# jeu_du_moulin_boura_uP_SCH.net
KiCad netlist of a schematic drawn in Altium Designer
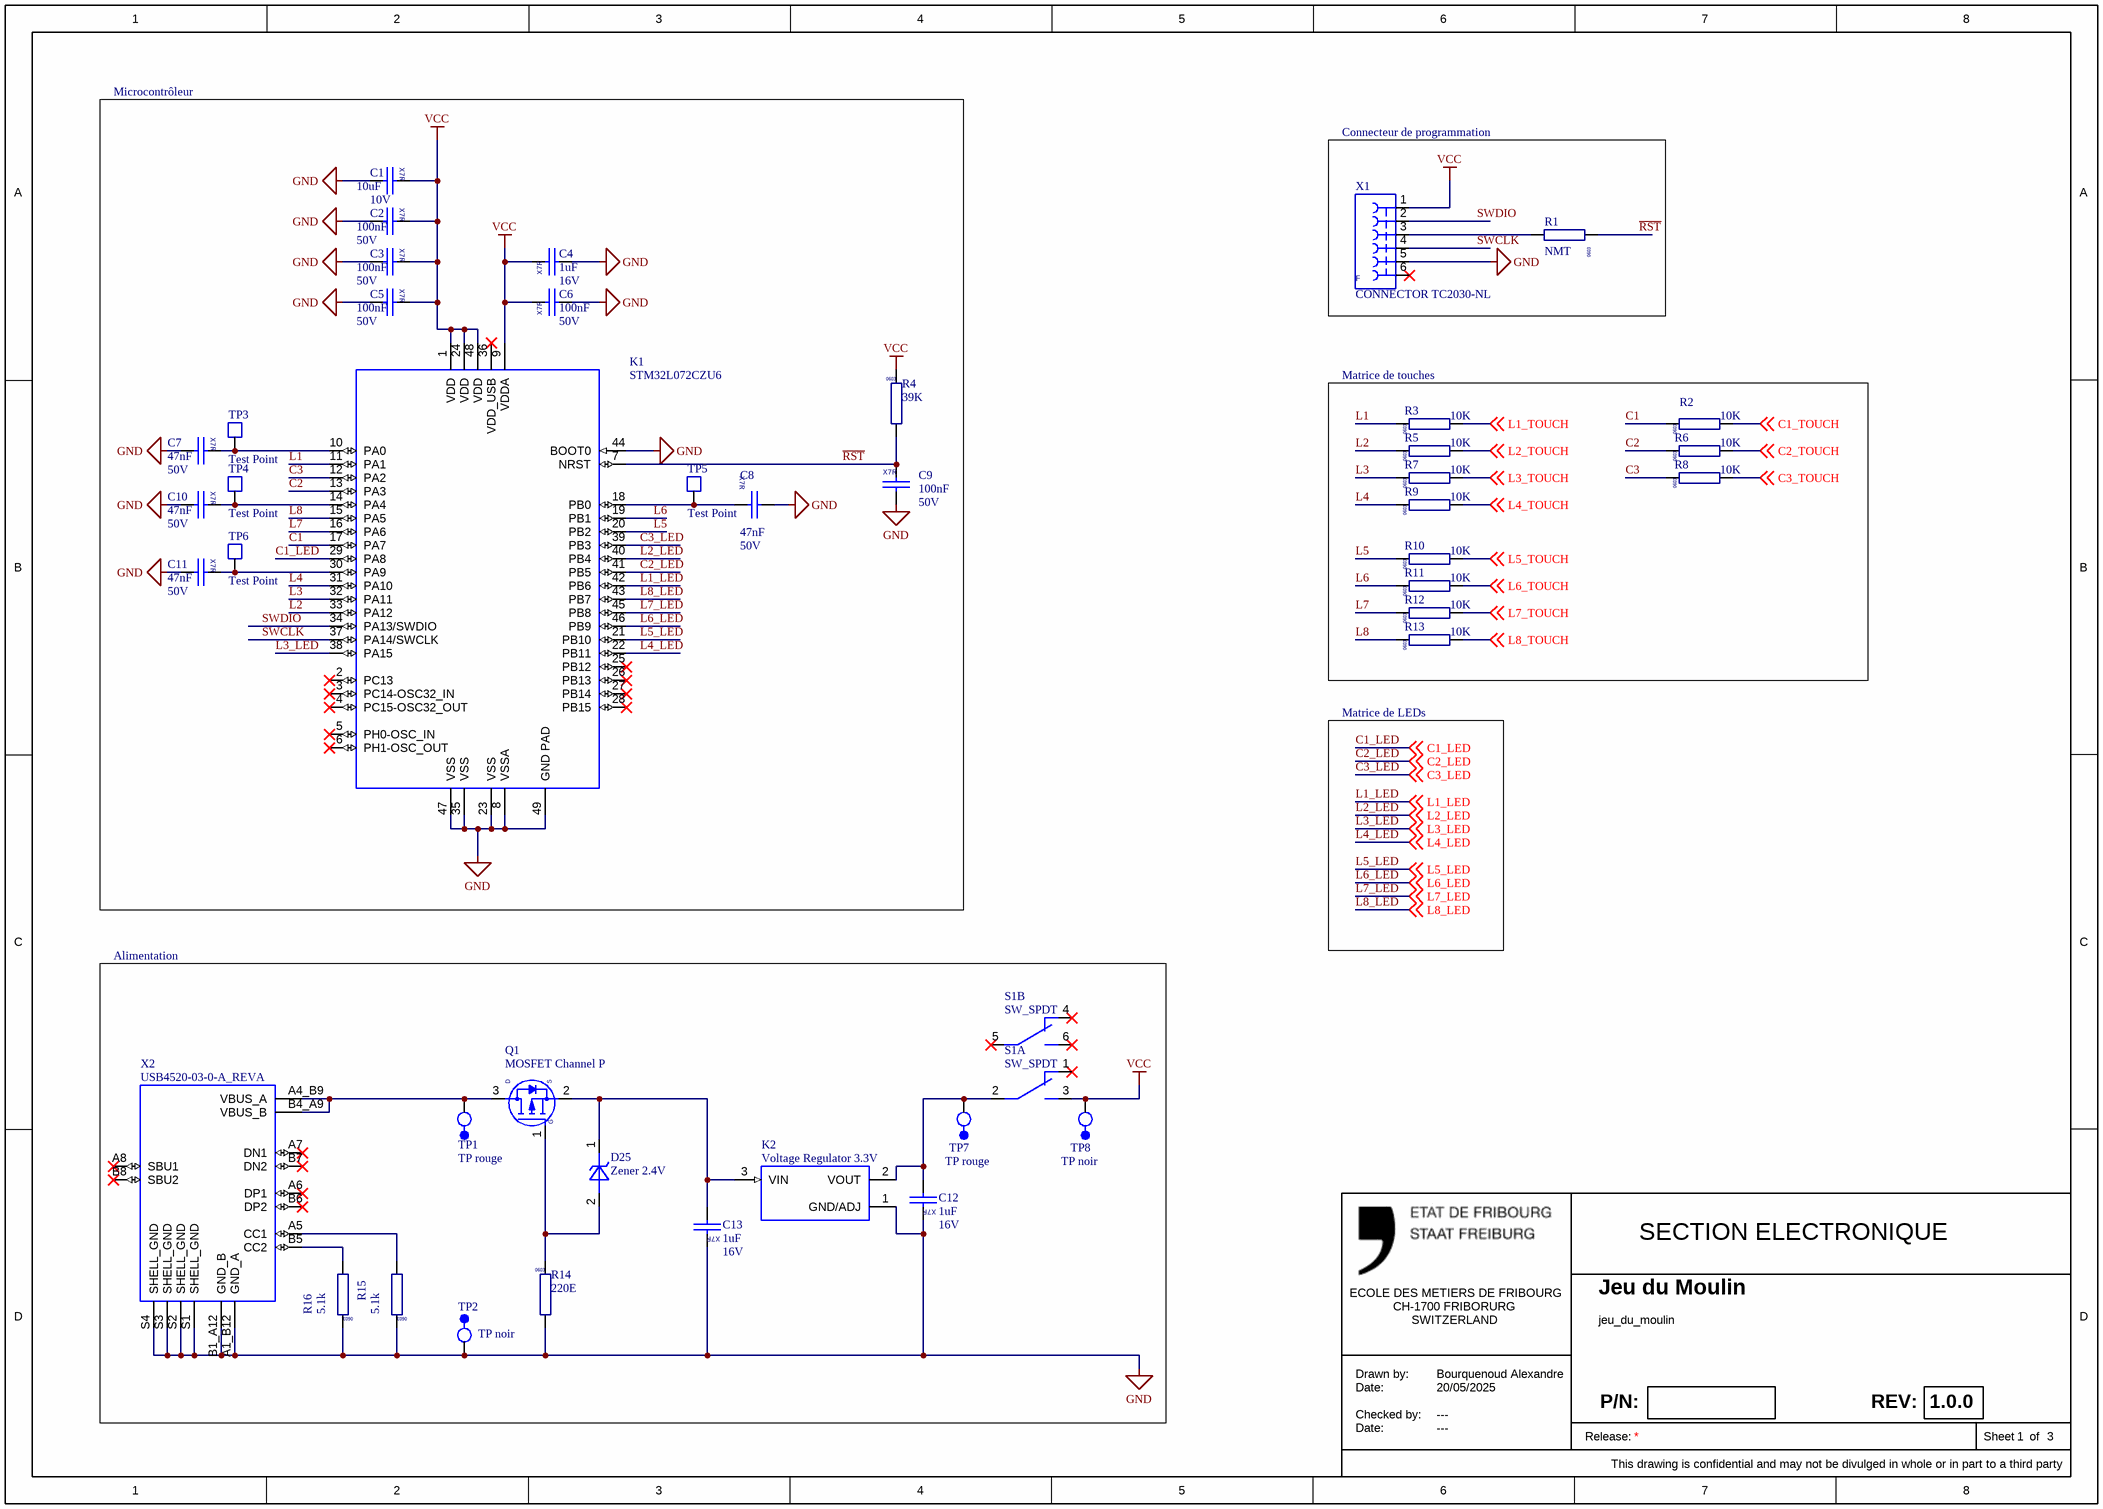
[diagram p0: jeu_du_moulin_boura_uP_SCH.SchDoc]

(export (version "E")
  (design (tool "Eeschema 10.0.6"))
  (components
    (comp (ref "C1")
      (value "10uF")
      (footprint "CSMD0603")
      (description "C X5R 10uF 20% 10V 0603")
      (fields (field (name "VOLT") "10V"))
      (libsource (lib "EMF_DataBase") (part "E_COND-X7R"))
    )
    (comp (ref "C2")
      (value "100nF")
      (footprint "CSMD0603")
      (description "C X7R 0.1uF 10% 50V 0603")
      (fields (field (name "VOLT") "50V"))
      (libsource (lib "EMF_DataBase") (part "E_COND-X7R"))
    )
    (comp (ref "C3")
      (value "100nF")
      (footprint "CSMD0603")
      (description "C X7R 0.1uF 10% 50V 0603")
      (fields (field (name "VOLT") "50V"))
      (libsource (lib "EMF_DataBase") (part "E_COND-X7R"))
    )
    (comp (ref "C4")
      (value "1uF")
      (footprint "CSMD0603")
      (description "C X7R 1uF 10% 16V 0603")
      (fields (field (name "VOLT") "16V"))
      (libsource (lib "EMF_DataBase") (part "E_COND-X7R"))
    )
    (comp (ref "C5")
      (value "100nF")
      (footprint "CSMD0603")
      (description "C X7R 0.1uF 10% 50V 0603")
      (fields (field (name "VOLT") "50V"))
      (libsource (lib "EMF_DataBase") (part "E_COND-X7R"))
    )
    (comp (ref "C6")
      (value "100nF")
      (footprint "CSMD0603")
      (description "C X7R 0.1uF 10% 50V 0603")
      (fields (field (name "VOLT") "50V"))
      (libsource (lib "EMF_DataBase") (part "E_COND-X7R"))
    )
    (comp (ref "C7")
      (value "47nF")
      (footprint "CSMD0603")
      (description "C X7R 47nF 10% 50V 0603")
      (fields (field (name "VOLT") "50V"))
      (libsource (lib "EMF_DataBase") (part "E_COND-X7R"))
    )
    (comp (ref "C8")
      (value "47nF")
      (footprint "CSMD0603")
      (description "C X7R 47nF 10% 50V 0603")
      (fields (field (name "VOLT") "50V"))
      (libsource (lib "EMF_DataBase") (part "E_COND-X7R"))
    )
    (comp (ref "C9")
      (value "100nF")
      (footprint "CSMD0603")
      (description "C X7R 0.1uF 10% 50V 0603")
      (fields (field (name "VOLT") "50V"))
      (libsource (lib "EMF_DataBase") (part "E_COND-X7R"))
    )
    (comp (ref "C10")
      (value "47nF")
      (footprint "CSMD0603")
      (description "C X7R 47nF 10% 50V 0603")
      (fields (field (name "VOLT") "50V"))
      (libsource (lib "EMF_DataBase") (part "E_COND-X7R"))
    )
    (comp (ref "C11")
      (value "47nF")
      (footprint "CSMD0603")
      (description "C X7R 47nF 10% 50V 0603")
      (fields (field (name "VOLT") "50V"))
      (libsource (lib "EMF_DataBase") (part "E_COND-X7R"))
    )
    (comp (ref "C12")
      (value "1uF")
      (footprint "CSMD0603")
      (description "C X7R 1uF 10% 16V 0603")
      (fields (field (name "VOLT") "16V"))
      (libsource (lib "EMF_DataBase") (part "E_COND-X7R"))
    )
    (comp (ref "C13")
      (value "1uF")
      (footprint "CSMD0603")
      (description "C X7R 1uF 10% 16V 0603")
      (fields (field (name "VOLT") "16V"))
      (libsource (lib "EMF_DataBase") (part "E_COND-X7R"))
    )
    (comp (ref "D25")
      (value "Zener 2.4V")
      (footprint "SOD-123")
      (description "Diodes - Zener 2.4 V 500 mW ±5% Montage en surface SOD-123")
      (libsource (lib "jeu_du_moulin_boura_INTLIB") (part "Zener 2.4V"))
    )
    (comp (ref "K1")
      (value "STM32L072CZU6")
      (footprint "UFQFPN48")
      (description "IC MCU 32BIT 192KB FLASH UFQFPN48s")
      (libsource (lib "jeu_du_moulin_boura_INTLIB") (part "STM32L072CZU6"))
    )
    (comp (ref "K2")
      (value "Voltage Regulator 3.3V")
      (footprint "SOT95P240X88-3N")
      (description "3.3-Volt Low Drop Out Voltage Regulatator")
      (libsource (lib "jeu_du_moulin_boura_INTLIB") (part "Voltage Regulator 3.3V"))
    )
    (comp (ref "Q1")
      (value "MOSFET Channel P")
      (footprint "SOT95P240X88-3N")
      (description "MOSFET Pch -80V -10A TO-252, Power MOSFET")
      (libsource (lib "jeu_du_moulin_boura_INTLIB") (part "MOSFET Channel P"))
    )
    (comp (ref "R1")
      (value "NMT")
      (footprint "RSMD0603")
      (description "R SMD NOT MOUNTED  1% 60mW  CHIP 0603")
      (fields (field (name "POWER") "60mW"))
      (libsource (lib "") (part "E_RSMD0603_1"))
    )
    (comp (ref "R2")
      (value "10K")
      (footprint "RSMD0603")
      (description "R SMD 10K  1%  60mW  CHIP 0603")
      (fields (field (name "POWER") "60mW"))
      (libsource (lib "EMF_DataBase") (part "E_RSMD0603"))
    )
    (comp (ref "R3")
      (value "10K")
      (footprint "RSMD0603")
      (description "R SMD 10K  1%  60mW  CHIP 0603")
      (fields (field (name "POWER") "60mW"))
      (libsource (lib "EMF_DataBase") (part "E_RSMD0603"))
    )
    (comp (ref "R4")
      (value "39K")
      (footprint "RSMD0603")
      (description "R SMD 39K  1%  60mW  CHIP 0603")
      (fields (field (name "POWER") "60mW"))
      (libsource (lib "") (part "E_RSMD0603_1"))
    )
    (comp (ref "R5")
      (value "10K")
      (footprint "RSMD0603")
      (description "R SMD 10K  1%  60mW  CHIP 0603")
      (fields (field (name "POWER") "60mW"))
      (libsource (lib "EMF_DataBase") (part "E_RSMD0603"))
    )
    (comp (ref "R6")
      (value "10K")
      (footprint "RSMD0603")
      (description "R SMD 10K  1%  60mW  CHIP 0603")
      (fields (field (name "POWER") "60mW"))
      (libsource (lib "EMF_DataBase") (part "E_RSMD0603"))
    )
    (comp (ref "R7")
      (value "10K")
      (footprint "RSMD0603")
      (description "R SMD 10K  1%  60mW  CHIP 0603")
      (fields (field (name "POWER") "60mW"))
      (libsource (lib "EMF_DataBase") (part "E_RSMD0603"))
    )
    (comp (ref "R8")
      (value "10K")
      (footprint "RSMD0603")
      (description "R SMD 10K  1%  60mW  CHIP 0603")
      (fields (field (name "POWER") "60mW"))
      (libsource (lib "EMF_DataBase") (part "E_RSMD0603"))
    )
    (comp (ref "R9")
      (value "10K")
      (footprint "RSMD0603")
      (description "R SMD 10K  1%  60mW  CHIP 0603")
      (fields (field (name "POWER") "60mW"))
      (libsource (lib "EMF_DataBase") (part "E_RSMD0603"))
    )
    (comp (ref "R10")
      (value "10K")
      (footprint "RSMD0603")
      (description "R SMD 10K  1%  60mW  CHIP 0603")
      (fields (field (name "POWER") "60mW"))
      (libsource (lib "EMF_DataBase") (part "E_RSMD0603"))
    )
    (comp (ref "R11")
      (value "10K")
      (footprint "RSMD0603")
      (description "R SMD 10K  1%  60mW  CHIP 0603")
      (fields (field (name "POWER") "60mW"))
      (libsource (lib "EMF_DataBase") (part "E_RSMD0603"))
    )
    (comp (ref "R12")
      (value "10K")
      (footprint "RSMD0603")
      (description "R SMD 10K  1%  60mW  CHIP 0603")
      (fields (field (name "POWER") "60mW"))
      (libsource (lib "EMF_DataBase") (part "E_RSMD0603"))
    )
    (comp (ref "R13")
      (value "10K")
      (footprint "RSMD0603")
      (description "R SMD 10K  1%  60mW  CHIP 0603")
      (fields (field (name "POWER") "60mW"))
      (libsource (lib "EMF_DataBase") (part "E_RSMD0603"))
    )
    (comp (ref "R14")
      (value "220E")
      (footprint "RSMD0603")
      (description "R SMD 220E  1% 60mW  CHIP 0603")
      (fields (field (name "POWER") "60mW"))
      (libsource (lib "") (part "E_RSMD0603_1"))
    )
    (comp (ref "R15")
      (value "5.1k")
      (footprint "RSMD0603")
      (description "5.1 kOhms ±1% 0,1W, 1/10W Pavé résistif 0603 (1608 métrique) AutomobileAEC-Q200 Couche épaisse")
      (libsource (lib "jeu_du_moulin_boura_INTLIB") (part "5.1k"))
    )
    (comp (ref "R16")
      (value "5.1k")
      (footprint "RSMD0603")
      (description "5.1 kOhms ±1% 0,1W, 1/10W Pavé résistif 0603 (1608 métrique) AutomobileAEC-Q200 Couche épaisse")
      (libsource (lib "jeu_du_moulin_boura_INTLIB") (part "5.1k"))
    )
    (comp (ref "S1")
      (value "SW_SPDT")
      (footprint "Switch Slide DPDT")
      (description "Switch slide SPDT 300mA 6V")
      (libsource (lib "jeu_du_moulin_boura_INTLIB") (part "SW_SPDT"))
    )
    (comp (ref "TP1")
      (value "TP rouge")
      (footprint "TP10_22")
      (description "Point de test CI isolé rouge")
      (libsource (lib "EMF_DataBase") (part "E_TestPoint_Sonde"))
    )
    (comp (ref "TP2")
      (value "TP noir")
      (footprint "TP10_22")
      (description "Point de test CI isolé noir")
      (libsource (lib "EMF_DataBase") (part "E_TestPoint_Sonde"))
    )
    (comp (ref "TP3")
      (value "Test Point")
      (footprint "TP")
      (description "Point de Test SMD")
      (libsource (lib "jeu_du_moulin_boura_INTLIB") (part "Test Point"))
    )
    (comp (ref "TP4")
      (value "Test Point")
      (footprint "TP")
      (description "Point de Test SMD")
      (libsource (lib "jeu_du_moulin_boura_INTLIB") (part "Test Point"))
    )
    (comp (ref "TP5")
      (value "Test Point")
      (footprint "TP")
      (description "Point de Test SMD")
      (libsource (lib "jeu_du_moulin_boura_INTLIB") (part "Test Point"))
    )
    (comp (ref "TP6")
      (value "Test Point")
      (footprint "TP")
      (description "Point de Test SMD")
      (libsource (lib "jeu_du_moulin_boura_INTLIB") (part "Test Point"))
    )
    (comp (ref "TP7")
      (value "TP rouge")
      (footprint "TP10_22")
      (description "Point de test CI isolé rouge")
      (libsource (lib "EMF_DataBase") (part "E_TestPoint_Sonde"))
    )
    (comp (ref "TP8")
      (value "TP noir")
      (footprint "TP10_22")
      (description "Point de test CI isolé noir")
      (libsource (lib "EMF_DataBase") (part "E_TestPoint_Sonde"))
    )
    (comp (ref "X1")
      (value "CONNECTOR TC2030-NL")
      (footprint "T-Connect 2030")
      (description "Connecteur pour TC2030-NL")
      (libsource (lib "jeu_du_moulin_boura_INTLIB") (part "CONNECTOR TC2030-NL"))
    )
    (comp (ref "X2")
      (value "USB4520-03-0-A_REVA")
      (footprint "GCT_USB4520-03-0-A_REVA")
      (libsource (lib "jeu_du_moulin_boura_INTLIB") (part "USB4520-03-0-A_REVA"))
    )
  )
  (nets
    (net (code "1") (name "/C1") (class "Default")
      (node (ref "K1") (pin "17") (pinfunction "PA7_17") (pintype "bidirectional"))
      (node (ref "R2") (pin "1") (pinfunction "1_1") (pintype "passive"))
    )
    (net (code "2") (name "/C2") (class "Default")
      (node (ref "K1") (pin "13") (pinfunction "PA3_13") (pintype "bidirectional"))
      (node (ref "R6") (pin "1") (pinfunction "1_1") (pintype "passive"))
    )
    (net (code "3") (name "/C3") (class "Default")
      (node (ref "K1") (pin "12") (pinfunction "PA2_12") (pintype "bidirectional"))
      (node (ref "R8") (pin "1") (pinfunction "1_1") (pintype "passive"))
    )
    (net (code "4") (name "/L1") (class "Default")
      (node (ref "K1") (pin "11") (pinfunction "PA1_11") (pintype "bidirectional"))
      (node (ref "R3") (pin "1") (pinfunction "1_1") (pintype "passive"))
    )
    (net (code "5") (name "/L2") (class "Default")
      (node (ref "K1") (pin "33") (pinfunction "PA12_33") (pintype "bidirectional"))
      (node (ref "R5") (pin "1") (pinfunction "1_1") (pintype "passive"))
    )
    (net (code "6") (name "/L3") (class "Default")
      (node (ref "K1") (pin "32") (pinfunction "PA11_32") (pintype "bidirectional"))
      (node (ref "R7") (pin "1") (pinfunction "1_1") (pintype "passive"))
    )
    (net (code "7") (name "/L4") (class "Default")
      (node (ref "K1") (pin "31") (pinfunction "PA10_31") (pintype "bidirectional"))
      (node (ref "R9") (pin "1") (pinfunction "1_1") (pintype "passive"))
    )
    (net (code "8") (name "/L5") (class "Default")
      (node (ref "K1") (pin "20") (pinfunction "PB2_20") (pintype "bidirectional"))
      (node (ref "R10") (pin "1") (pinfunction "1_1") (pintype "passive"))
    )
    (net (code "9") (name "/L6") (class "Default")
      (node (ref "K1") (pin "19") (pinfunction "PB1_19") (pintype "bidirectional"))
      (node (ref "R11") (pin "1") (pinfunction "1_1") (pintype "passive"))
    )
    (net (code "10") (name "/L7") (class "Default")
      (node (ref "K1") (pin "16") (pinfunction "PA6_16") (pintype "bidirectional"))
      (node (ref "R12") (pin "1") (pinfunction "1_1") (pintype "passive"))
    )
    (net (code "11") (name "/L8") (class "Default")
      (node (ref "K1") (pin "15") (pinfunction "PA5_15") (pintype "bidirectional"))
      (node (ref "R13") (pin "1") (pinfunction "1_1") (pintype "passive"))
    )
    (net (code "12") (name "/SWCLK") (class "Default")
      (node (ref "K1") (pin "37") (pinfunction "PA14/SWCLK_37") (pintype "bidirectional"))
      (node (ref "X1") (pin "4") (pinfunction "SWCLK_4") (pintype "passive"))
    )
    (net (code "13") (name "/SWDIO") (class "Default")
      (node (ref "K1") (pin "34") (pinfunction "PA13/SWDIO_34") (pintype "bidirectional"))
      (node (ref "X1") (pin "2") (pinfunction "SWDIO_2") (pintype "passive"))
    )
    (net (code "14") (name "/~{RST}") (class "Default")
      (node (ref "C9") (pin "1") (pinfunction "1_1") (pintype "passive"))
      (node (ref "K1") (pin "7") (pinfunction "NRST_7") (pintype "bidirectional"))
      (node (ref "R1") (pin "1") (pinfunction "1_1") (pintype "passive"))
      (node (ref "R4") (pin "2") (pinfunction "2_2") (pintype "passive"))
    )
    (net (code "15") (name "C1_LED") (class "Default")
      (node (ref "K1") (pin "29") (pinfunction "PA8_29") (pintype "bidirectional"))
    )
    (net (code "16") (name "C1_TOUCH") (class "Default")
      (node (ref "R2") (pin "2") (pinfunction "2_2") (pintype "passive"))
    )
    (net (code "17") (name "C2_LED") (class "Default")
      (node (ref "K1") (pin "41") (pinfunction "PB5_41") (pintype "bidirectional"))
    )
    (net (code "18") (name "C2_TOUCH") (class "Default")
      (node (ref "R6") (pin "2") (pinfunction "2_2") (pintype "passive"))
    )
    (net (code "19") (name "C3_LED") (class "Default")
      (node (ref "K1") (pin "39") (pinfunction "PB3_39") (pintype "bidirectional"))
    )
    (net (code "20") (name "C3_TOUCH") (class "Default")
      (node (ref "R8") (pin "2") (pinfunction "2_2") (pintype "passive"))
    )
    (net (code "21") (name "GND") (class "Default")
      (node (ref "C1") (pin "2") (pinfunction "2_2") (pintype "passive"))
      (node (ref "C10") (pin "2") (pinfunction "2_2") (pintype "passive"))
      (node (ref "C11") (pin "2") (pinfunction "2_2") (pintype "passive"))
      (node (ref "C12") (pin "1") (pinfunction "1_1") (pintype "passive"))
      (node (ref "C13") (pin "1") (pinfunction "1_1") (pintype "passive"))
      (node (ref "C2") (pin "2") (pinfunction "2_2") (pintype "passive"))
      (node (ref "C3") (pin "2") (pinfunction "2_2") (pintype "passive"))
      (node (ref "C4") (pin "2") (pinfunction "2_2") (pintype "passive"))
      (node (ref "C5") (pin "2") (pinfunction "2_2") (pintype "passive"))
      (node (ref "C6") (pin "2") (pinfunction "2_2") (pintype "passive"))
      (node (ref "C7") (pin "2") (pinfunction "2_2") (pintype "passive"))
      (node (ref "C8") (pin "2") (pinfunction "2_2") (pintype "passive"))
      (node (ref "C9") (pin "2") (pinfunction "2_2") (pintype "passive"))
      (node (ref "K1") (pin "23") (pinfunction "VSS_23") (pintype "power_in"))
      (node (ref "K1") (pin "35") (pinfunction "VSS_35") (pintype "power_in"))
      (node (ref "K1") (pin "44") (pinfunction "BOOT0_44") (pintype "input"))
      (node (ref "K1") (pin "47") (pinfunction "VSS_47") (pintype "power_in"))
      (node (ref "K1") (pin "49") (pinfunction "GND_PAD_49") (pintype "power_in"))
      (node (ref "K1") (pin "8") (pinfunction "VSSA_8") (pintype "power_in"))
      (node (ref "K2") (pin "1") (pinfunction "GND/ADJ_1") (pintype "power_in"))
      (node (ref "R14") (pin "2") (pinfunction "2_2") (pintype "passive"))
      (node (ref "R15") (pin "1") (pinfunction "1_1") (pintype "passive"))
      (node (ref "R16") (pin "1") (pinfunction "1_1") (pintype "passive"))
      (node (ref "TP2") (pin "1") (pinfunction "a_1") (pintype "passive"))
      (node (ref "X1") (pin "5") (pinfunction "GND_5") (pintype "passive"))
      (node (ref "X2") (pin "A1_B12") (pinfunction "GND_A_A1_B12") (pintype "power_in"))
      (node (ref "X2") (pin "B1_A12") (pinfunction "GND_B_B1_A12") (pintype "power_in"))
      (node (ref "X2") (pin "S1") (pinfunction "SHELL_GND_S1") (pintype "power_in"))
      (node (ref "X2") (pin "S2") (pinfunction "SHELL_GND_S2") (pintype "power_in"))
      (node (ref "X2") (pin "S3") (pinfunction "SHELL_GND_S3") (pintype "power_in"))
      (node (ref "X2") (pin "S4") (pinfunction "SHELL_GND_S4") (pintype "power_in"))
    )
    (net (code "22") (name "L1_LED") (class "Default")
      (node (ref "K1") (pin "42") (pinfunction "PB6_42") (pintype "bidirectional"))
    )
    (net (code "23") (name "L1_TOUCH") (class "Default")
      (node (ref "R3") (pin "2") (pinfunction "2_2") (pintype "passive"))
    )
    (net (code "24") (name "L2_LED") (class "Default")
      (node (ref "K1") (pin "40") (pinfunction "PB4_40") (pintype "bidirectional"))
    )
    (net (code "25") (name "L2_TOUCH") (class "Default")
      (node (ref "R5") (pin "2") (pinfunction "2_2") (pintype "passive"))
    )
    (net (code "26") (name "L3_LED") (class "Default")
      (node (ref "K1") (pin "38") (pinfunction "PA15_38") (pintype "bidirectional"))
    )
    (net (code "27") (name "L3_TOUCH") (class "Default")
      (node (ref "R7") (pin "2") (pinfunction "2_2") (pintype "passive"))
    )
    (net (code "28") (name "L4_LED") (class "Default")
      (node (ref "K1") (pin "22") (pinfunction "PB11_22") (pintype "bidirectional"))
    )
    (net (code "29") (name "L4_TOUCH") (class "Default")
      (node (ref "R9") (pin "2") (pinfunction "2_2") (pintype "passive"))
    )
    (net (code "30") (name "L5_LED") (class "Default")
      (node (ref "K1") (pin "21") (pinfunction "PB10_21") (pintype "bidirectional"))
    )
    (net (code "31") (name "L5_TOUCH") (class "Default")
      (node (ref "R10") (pin "2") (pinfunction "2_2") (pintype "passive"))
    )
    (net (code "32") (name "L6_LED") (class "Default")
      (node (ref "K1") (pin "46") (pinfunction "PB9_46") (pintype "bidirectional"))
    )
    (net (code "33") (name "L6_TOUCH") (class "Default")
      (node (ref "R11") (pin "2") (pinfunction "2_2") (pintype "passive"))
    )
    (net (code "34") (name "L7_LED") (class "Default")
      (node (ref "K1") (pin "45") (pinfunction "PB8_45") (pintype "bidirectional"))
    )
    (net (code "35") (name "L7_TOUCH") (class "Default")
      (node (ref "R12") (pin "2") (pinfunction "2_2") (pintype "passive"))
    )
    (net (code "36") (name "L8_LED") (class "Default")
      (node (ref "K1") (pin "43") (pinfunction "PB7_43") (pintype "bidirectional"))
    )
    (net (code "37") (name "L8_TOUCH") (class "Default")
      (node (ref "R13") (pin "2") (pinfunction "2_2") (pintype "passive"))
    )
    (net (code "38") (name "Net-(D25-ANODE)") (class "Default")
      (node (ref "D25") (pin "2") (pinfunction "ANODE_2") (pintype "passive"))
      (node (ref "Q1") (pin "1") (pinfunction "Gate_1") (pintype "passive"))
      (node (ref "R14") (pin "1") (pinfunction "1_1") (pintype "passive"))
    )
    (net (code "39") (name "Net-(D25-CATHODE)") (class "Default")
      (node (ref "C13") (pin "2") (pinfunction "2_2") (pintype "passive"))
      (node (ref "D25") (pin "1") (pinfunction "CATHODE_1") (pintype "passive"))
      (node (ref "K2") (pin "3") (pinfunction "VIN_3") (pintype "input"))
      (node (ref "Q1") (pin "2") (pinfunction "Drain_2") (pintype "passive"))
    )
    (net (code "40") (name "Net-(K1-PA0)") (class "Default")
      (node (ref "C7") (pin "1") (pinfunction "1_1") (pintype "passive"))
      (node (ref "K1") (pin "10") (pinfunction "PA0_10") (pintype "bidirectional"))
      (node (ref "TP3") (pin "1") (pinfunction "a_1") (pintype "passive"))
    )
    (net (code "41") (name "Net-(K1-PA4)") (class "Default")
      (node (ref "C10") (pin "1") (pinfunction "1_1") (pintype "passive"))
      (node (ref "K1") (pin "14") (pinfunction "PA4_14") (pintype "bidirectional"))
      (node (ref "TP4") (pin "1") (pinfunction "a_1") (pintype "passive"))
    )
    (net (code "42") (name "Net-(K1-PA9)") (class "Default")
      (node (ref "C11") (pin "1") (pinfunction "1_1") (pintype "passive"))
      (node (ref "K1") (pin "30") (pinfunction "PA9_30") (pintype "bidirectional"))
      (node (ref "TP6") (pin "1") (pinfunction "a_1") (pintype "passive"))
    )
    (net (code "43") (name "Net-(K1-PB0)") (class "Default")
      (node (ref "C8") (pin "1") (pinfunction "1_1") (pintype "passive"))
      (node (ref "K1") (pin "18") (pinfunction "PB0_18") (pintype "bidirectional"))
      (node (ref "TP5") (pin "1") (pinfunction "a_1") (pintype "passive"))
    )
    (net (code "44") (name "Net-(K2-VOUT)") (class "Default")
      (node (ref "C12") (pin "2") (pinfunction "2_2") (pintype "passive"))
      (node (ref "K2") (pin "2") (pinfunction "VOUT_2") (pintype "power_in"))
      (node (ref "S1") (pin "2") (pinfunction "2_2") (pintype "passive"))
      (node (ref "TP7") (pin "1") (pinfunction "a_1") (pintype "passive"))
    )
    (net (code "45") (name "Net-(Q1-Source)") (class "Default")
      (node (ref "Q1") (pin "3") (pinfunction "Source_3") (pintype "passive"))
      (node (ref "TP1") (pin "1") (pinfunction "a_1") (pintype "passive"))
      (node (ref "X2") (pin "A4_B9") (pinfunction "VBUS_A_A4_B9") (pintype "power_in"))
      (node (ref "X2") (pin "B4_A9") (pinfunction "VBUS_B_B4_A9") (pintype "power_in"))
    )
    (net (code "46") (name "Net-(X1-NMVLR{slash}RESET)") (class "Default")
      (node (ref "R1") (pin "2") (pinfunction "2_2") (pintype "passive"))
      (node (ref "X1") (pin "3") (pinfunction "NMVLR/RESET_3") (pintype "passive"))
    )
    (net (code "47") (name "Net-(X2-CC1)") (class "Default")
      (node (ref "R15") (pin "2") (pinfunction "2_2") (pintype "passive"))
      (node (ref "X2") (pin "A5") (pinfunction "CC1_A5") (pintype "bidirectional"))
    )
    (net (code "48") (name "Net-(X2-CC2)") (class "Default")
      (node (ref "R16") (pin "2") (pinfunction "2_2") (pintype "passive"))
      (node (ref "X2") (pin "B5") (pinfunction "CC2_B5") (pintype "bidirectional"))
    )
    (net (code "49") (name "VCC") (class "Default")
      (node (ref "C1") (pin "1") (pinfunction "1_1") (pintype "passive"))
      (node (ref "C2") (pin "1") (pinfunction "1_1") (pintype "passive"))
      (node (ref "C3") (pin "1") (pinfunction "1_1") (pintype "passive"))
      (node (ref "C4") (pin "1") (pinfunction "1_1") (pintype "passive"))
      (node (ref "C5") (pin "1") (pinfunction "1_1") (pintype "passive"))
      (node (ref "C6") (pin "1") (pinfunction "1_1") (pintype "passive"))
      (node (ref "K1") (pin "1") (pinfunction "VDD_1") (pintype "power_in"))
      (node (ref "K1") (pin "24") (pinfunction "VDD_24") (pintype "power_in"))
      (node (ref "K1") (pin "48") (pinfunction "VDD_48") (pintype "power_in"))
      (node (ref "K1") (pin "9") (pinfunction "VDDA_9") (pintype "power_in"))
      (node (ref "R4") (pin "1") (pinfunction "1_1") (pintype "passive"))
      (node (ref "S1") (pin "3") (pinfunction "3_3") (pintype "passive"))
      (node (ref "TP8") (pin "1") (pinfunction "a_1") (pintype "passive"))
      (node (ref "X1") (pin "1") (pinfunction "VDD_VIOREF_1") (pintype "passive"))
    )
    (net (code "50") (name "unconnected-(K1-PB12-Pad25)") (class "Default")
      (node (ref "K1") (pin "25") (pinfunction "PB12_25") (pintype "bidirectional+no_connect"))
    )
    (net (code "51") (name "unconnected-(K1-PB13-Pad26)") (class "Default")
      (node (ref "K1") (pin "26") (pinfunction "PB13_26") (pintype "bidirectional+no_connect"))
    )
    (net (code "52") (name "unconnected-(K1-PB14-Pad27)") (class "Default")
      (node (ref "K1") (pin "27") (pinfunction "PB14_27") (pintype "bidirectional+no_connect"))
    )
    (net (code "53") (name "unconnected-(K1-PB15-Pad28)") (class "Default")
      (node (ref "K1") (pin "28") (pinfunction "PB15_28") (pintype "bidirectional+no_connect"))
    )
    (net (code "54") (name "unconnected-(K1-PC13-Pad2)") (class "Default")
      (node (ref "K1") (pin "2") (pinfunction "PC13_2") (pintype "bidirectional+no_connect"))
    )
    (net (code "55") (name "unconnected-(K1-PC14-OSC32_IN-Pad3)") (class "Default")
      (node (ref "K1") (pin "3") (pinfunction "PC14-OSC32_IN_3") (pintype "bidirectional+no_connect"))
    )
    (net (code "56") (name "unconnected-(K1-PC15-OSC32_OUT-Pad4)") (class "Default")
      (node (ref "K1") (pin "4") (pinfunction "PC15-OSC32_OUT_4") (pintype "bidirectional+no_connect"))
    )
    (net (code "57") (name "unconnected-(K1-PH0-OSC_IN-Pad5)") (class "Default")
      (node (ref "K1") (pin "5") (pinfunction "PH0-OSC_IN_5") (pintype "bidirectional+no_connect"))
    )
    (net (code "58") (name "unconnected-(K1-PH1-OSC_OUT-Pad6)") (class "Default")
      (node (ref "K1") (pin "6") (pinfunction "PH1-OSC_OUT_6") (pintype "bidirectional+no_connect"))
    )
    (net (code "59") (name "unconnected-(K1-VDD_USB-Pad36)") (class "Default")
      (node (ref "K1") (pin "36") (pinfunction "VDD_USB_36") (pintype "power_in+no_connect"))
    )
    (net (code "60") (name "unconnected-(S1-Pad1)") (class "Default")
      (node (ref "S1") (pin "1") (pinfunction "1_1") (pintype "passive+no_connect"))
    )
    (net (code "61") (name "unconnected-(S1-Pad4)") (class "Default")
      (node (ref "S1") (pin "4") (pinfunction "4_4") (pintype "passive+no_connect"))
    )
    (net (code "62") (name "unconnected-(S1-Pad5)") (class "Default")
      (node (ref "S1") (pin "5") (pinfunction "5_5") (pintype "passive+no_connect"))
    )
    (net (code "63") (name "unconnected-(S1-Pad6)") (class "Default")
      (node (ref "S1") (pin "6") (pinfunction "6_6") (pintype "passive+no_connect"))
    )
    (net (code "64") (name "unconnected-(X1-SWO-Pad6)") (class "Default")
      (node (ref "X1") (pin "6") (pinfunction "SWO_6") (pintype "passive+no_connect"))
    )
    (net (code "65") (name "unconnected-(X2-DN1-PadA7)") (class "Default")
      (node (ref "X2") (pin "A7") (pinfunction "DN1_A7") (pintype "bidirectional+no_connect"))
    )
    (net (code "66") (name "unconnected-(X2-DN2-PadB7)") (class "Default")
      (node (ref "X2") (pin "B7") (pinfunction "DN2_B7") (pintype "bidirectional+no_connect"))
    )
    (net (code "67") (name "unconnected-(X2-DP1-PadA6)") (class "Default")
      (node (ref "X2") (pin "A6") (pinfunction "DP1_A6") (pintype "bidirectional+no_connect"))
    )
    (net (code "68") (name "unconnected-(X2-DP2-PadB6)") (class "Default")
      (node (ref "X2") (pin "B6") (pinfunction "DP2_B6") (pintype "bidirectional+no_connect"))
    )
    (net (code "69") (name "unconnected-(X2-SBU1-PadA8)") (class "Default")
      (node (ref "X2") (pin "A8") (pinfunction "SBU1_A8") (pintype "bidirectional+no_connect"))
    )
    (net (code "70") (name "unconnected-(X2-SBU2-PadB8)") (class "Default")
      (node (ref "X2") (pin "B8") (pinfunction "SBU2_B8") (pintype "bidirectional+no_connect"))
    )
  )
)
